# OK1050-C_V1_2_Usb.net
KiCad netlist of a schematic drawn in Altium Designer
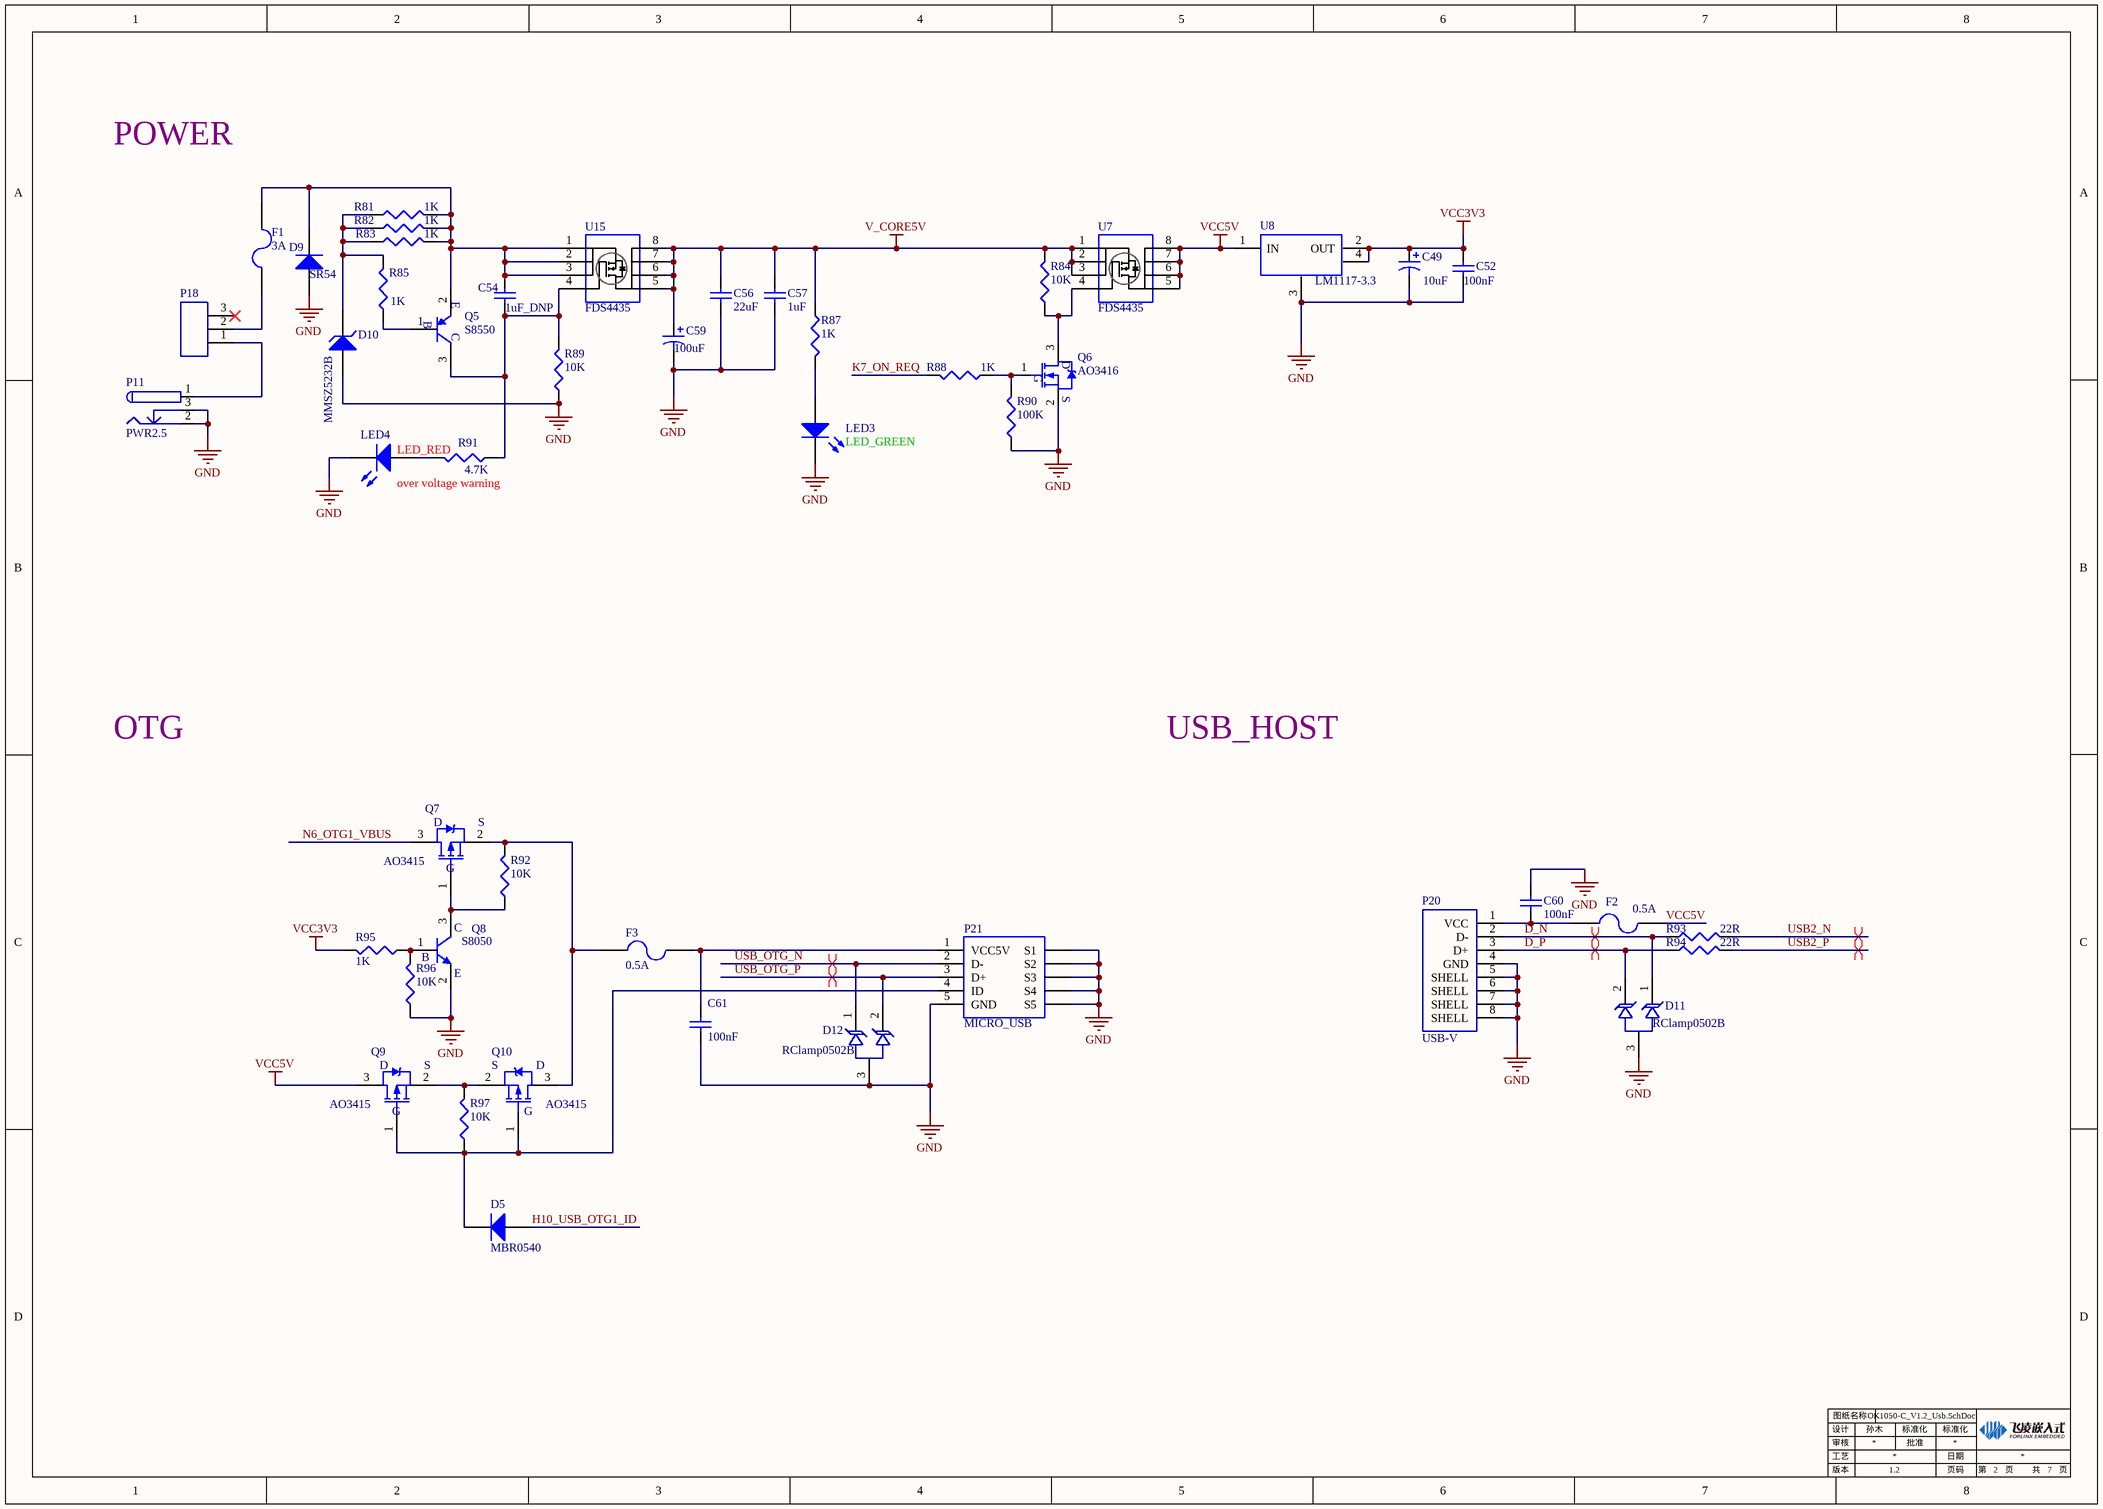
[diagram p0: OK1050-C_V1.2_Usb.SchDoc]

(export (version "E")
  (design (tool "Eeschema 10.0.6"))
  (components
    (comp (ref "C49")
      (value "10uF")
      (footprint "TC3216A")
      (description "Polarized Capacitor (Radial)")
      (fields (field (name "PUBLISHER") "Altium Limited"))
      (libsource (lib "Miscellaneous Devices") (part "Cap Pol1"))
    )
    (comp (ref "C52")
      (value "100nF")
      (footprint "0603C+")
      (description "Capacitor")
      (fields (field (name "PUBLISHER") "Altium Limited"))
      (libsource (lib "Miscellaneous Devices") (part "Cap"))
    )
    (comp (ref "C54")
      (value "1uF_DNP")
      (footprint "0603C+")
      (description "Capacitor")
      (fields (field (name "PUBLISHER") "Altium Limited"))
      (libsource (lib "Miscellaneous Devices") (part "Cap"))
    )
    (comp (ref "C56")
      (value "22uF")
      (footprint "0603C+")
      (description "Capacitor")
      (fields (field (name "PUBLISHER") "Altium Limited"))
      (libsource (lib "Miscellaneous Devices") (part "Cap"))
    )
    (comp (ref "C57")
      (value "1uF")
      (footprint "0603C+")
      (description "Capacitor")
      (fields (field (name "PUBLISHER") "Altium Limited"))
      (libsource (lib "Miscellaneous Devices") (part "Cap"))
    )
    (comp (ref "C59")
      (value "100uF")
      (footprint "TC3528B")
      (description "Polarized Capacitor (Radial)")
      (fields (field (name "PUBLISHER") "Altium Limited"))
      (libsource (lib "Miscellaneous Devices") (part "Cap Pol1"))
    )
    (comp (ref "C60")
      (value "100nF")
      (footprint "0603C+")
      (description "Capacitor")
      (fields (field (name "PUBLISHER") "Altium Limited"))
      (libsource (lib "Miscellaneous Devices") (part "Cap"))
    )
    (comp (ref "C61")
      (value "100nF")
      (footprint "0603C+")
      (description "Capacitor")
      (fields (field (name "PUBLISHER") "Altium Limited"))
      (libsource (lib "Miscellaneous Devices") (part "Cap"))
    )
    (comp (ref "D5")
      (value "MBR0540")
      (footprint "Diode1.6*2.6")
      (description "Default Diode")
      (fields (field (name "PUBLISHER") "Altium Limited"))
      (libsource (lib "Miscellaneous Devices") (part "Diode"))
    )
    (comp (ref "D9")
      (value "SR54")
      (footprint "SMB/DO-214AA")
      (description "Default Diode")
      (fields (field (name "PUBLISHER") "Altium Limited"))
      (libsource (lib "Miscellaneous Devices") (part "Diode"))
    )
    (comp (ref "D10")
      (value "MMSZ5232B")
      (footprint "Diode1.6*2.6")
      (description "Zener Diode")
      (fields (field (name "PUBLISHER") "Altium Limited"))
      (libsource (lib "Miscellaneous Devices") (part "D Zener"))
    )
    (comp (ref "D11") (value "RClamp0502B") (footprint "SOT-523") (libsource (lib "Sch") (part "LCTVS")))
    (comp (ref "D12") (value "RClamp0502B") (footprint "SOT-523") (libsource (lib "Sch") (part "LCTVS")))
    (comp (ref "F1")
      (value "3A")
      (footprint "R_1210")
      (description "Fuse")
      (fields (field (name "PUBLISHER") "Altium Limited"))
      (libsource (lib "Miscellaneous Devices") (part "Fuse 2"))
    )
    (comp (ref "F2")
      (value "0.5A")
      (footprint "R_1210")
      (description "Fuse")
      (fields (field (name "PUBLISHER") "Altium Limited"))
      (libsource (lib "Miscellaneous Devices") (part "Fuse 2"))
    )
    (comp (ref "F3")
      (value "0.5A")
      (footprint "R_1210")
      (description "Fuse")
      (fields (field (name "PUBLISHER") "Altium Limited"))
      (libsource (lib "Miscellaneous Devices") (part "Fuse 2"))
    )
    (comp (ref "LED3")
      (value "LED_GREEN")
      (footprint "LED0603_M1608")
      (description "Typical RED, GREEN, YELLOW, AMBER GaAs LED")
      (fields (field (name "PUBLISHER") "Altium Limited"))
      (libsource (lib "Miscellaneous Devices") (part "LED2"))
    )
    (comp (ref "LED4")
      (value "LED_RED")
      (footprint "LED0603_M1608")
      (description "Typical RED, GREEN, YELLOW, AMBER GaAs LED")
      (fields (field (name "PUBLISHER") "Altium Limited"))
      (libsource (lib "Miscellaneous Devices") (part "LED2"))
    )
    (comp (ref "P11") (value "PWR2.5") (footprint "JACK-2.5MM_B") (libsource (lib "Sch") (part "PWR2.5")))
    (comp (ref "P18") (value "P18") (footprint "SW01") (libsource (lib "Sch") (part "CON3")))
    (comp (ref "P20") (value "USB-V") (footprint "USB-C") (libsource (lib "IMX6QP-C") (part "USB-V")))
    (comp (ref "P21")
      (value "MICRO_USB")
      (footprint "microUSB")
      (description "Header, 5-Pin, Dual row")
      (fields (field (name "PUBLISHER") "Altium Limited"))
      (libsource (lib "PCB_RT1052") (part "MICRO_USB"))
    )
    (comp (ref "Q5")
      (value "S8550")
      (footprint "SOT95P245X110-3N")
      (description "NPN Bipolar Transistor")
      (fields (field (name "PUBLISHER") "Altium Limited"))
      (libsource (lib "KQX6A") (part "PNP"))
    )
    (comp (ref "Q6")
      (value "AO3416")
      (footprint "SOT95P245X110-3N")
      (description "N-Channel Power MOSFET")
      (fields (field (name "PUBLISHER") "Altium Limited"))
      (libsource (lib "IMX6QP-C") (part "NMOS"))
    )
    (comp (ref "Q7")
      (value "AO3415")
      (footprint "SOT95P245X110-3N")
      (description "N-Channel Power MOSFET")
      (fields (field (name "PUBLISHER") "Altium Limited"))
      (libsource (lib "KQX6A") (part "PMOS"))
    )
    (comp (ref "Q8")
      (value "S8050")
      (footprint "SOT95P245X110-3N")
      (description "NPN Bipolar Transistor")
      (fields (field (name "PUBLISHER") "Altium Limited"))
      (libsource (lib "KQX6A") (part "NPN"))
    )
    (comp (ref "Q9")
      (value "AO3415")
      (footprint "SOT95P245X110-3N")
      (description "N-Channel Power MOSFET")
      (fields (field (name "PUBLISHER") "Altium Limited"))
      (libsource (lib "KQX6A") (part "PMOS"))
    )
    (comp (ref "Q10")
      (value "AO3415")
      (footprint "SOT95P245X110-3N")
      (description "N-Channel Power MOSFET")
      (fields (field (name "PUBLISHER") "Altium Limited"))
      (libsource (lib "KQX6A") (part "PMOS"))
    )
    (comp (ref "R81")
      (value "1K")
      (footprint "0603R+")
      (description "Resistor")
      (fields (field (name "PUBLISHER") "Altium Limited"))
      (libsource (lib "Miscellaneous Devices") (part "Res3"))
    )
    (comp (ref "R82")
      (value "1K")
      (footprint "0603R+")
      (description "Resistor")
      (fields (field (name "PUBLISHER") "Altium Limited"))
      (libsource (lib "Miscellaneous Devices") (part "Res3"))
    )
    (comp (ref "R83")
      (value "1K")
      (footprint "0603R+")
      (description "Resistor")
      (fields (field (name "PUBLISHER") "Altium Limited"))
      (libsource (lib "Miscellaneous Devices") (part "Res3"))
    )
    (comp (ref "R84")
      (value "10K")
      (footprint "0603R+")
      (description "Resistor")
      (fields (field (name "PUBLISHER") "Altium Limited"))
      (libsource (lib "Miscellaneous Devices") (part "Res3"))
    )
    (comp (ref "R85")
      (value "1K")
      (footprint "0603R+")
      (description "Resistor")
      (fields (field (name "PUBLISHER") "Altium Limited"))
      (libsource (lib "Miscellaneous Devices") (part "Res3"))
    )
    (comp (ref "R87")
      (value "1K")
      (footprint "0603R+")
      (description "Resistor")
      (fields (field (name "PUBLISHER") "Altium Limited"))
      (libsource (lib "Miscellaneous Devices") (part "Res3"))
    )
    (comp (ref "R88")
      (value "1K")
      (footprint "0603R+")
      (description "Resistor")
      (fields (field (name "PUBLISHER") "Altium Limited"))
      (libsource (lib "Miscellaneous Devices") (part "Res3"))
    )
    (comp (ref "R89")
      (value "10K")
      (footprint "0603R+")
      (description "Resistor")
      (fields (field (name "PUBLISHER") "Altium Limited"))
      (libsource (lib "Miscellaneous Devices") (part "Res3"))
    )
    (comp (ref "R90")
      (value "100K")
      (footprint "0603R+")
      (description "Resistor")
      (fields (field (name "PUBLISHER") "Altium Limited"))
      (libsource (lib "Miscellaneous Devices") (part "Res3"))
    )
    (comp (ref "R91")
      (value "4.7K")
      (footprint "0603R+")
      (description "Resistor")
      (fields (field (name "PUBLISHER") "Altium Limited"))
      (libsource (lib "Miscellaneous Devices") (part "Res3"))
    )
    (comp (ref "R92")
      (value "10K")
      (footprint "0603R+")
      (description "Resistor")
      (fields (field (name "PUBLISHER") "Altium Limited"))
      (libsource (lib "Miscellaneous Devices") (part "Res3"))
    )
    (comp (ref "R93")
      (value "22R")
      (footprint "0603R+")
      (description "Resistor")
      (fields (field (name "PUBLISHER") "Altium Limited"))
      (libsource (lib "Miscellaneous Devices") (part "Res3"))
    )
    (comp (ref "R94")
      (value "22R")
      (footprint "0603R+")
      (description "Resistor")
      (fields (field (name "PUBLISHER") "Altium Limited"))
      (libsource (lib "Miscellaneous Devices") (part "Res3"))
    )
    (comp (ref "R95")
      (value "1K")
      (footprint "0603R+")
      (description "Resistor")
      (fields (field (name "PUBLISHER") "Altium Limited"))
      (libsource (lib "Miscellaneous Devices") (part "Res3"))
    )
    (comp (ref "R96")
      (value "10K")
      (footprint "0603R+")
      (description "Resistor")
      (fields (field (name "PUBLISHER") "Altium Limited"))
      (libsource (lib "Miscellaneous Devices") (part "Res3"))
    )
    (comp (ref "R97")
      (value "10K")
      (footprint "0603R+")
      (description "Resistor")
      (fields (field (name "PUBLISHER") "Altium Limited"))
      (libsource (lib "Miscellaneous Devices") (part "Res3"))
    )
    (comp (ref "U7") (value "FDS4435") (footprint "FDS4435") (libsource (lib "OK5718") (part "FDS4435")))
    (comp (ref "U8") (value "LM1117-3.3") (footprint "LM1117") (libsource (lib "Sch") (part "LM1117")))
    (comp (ref "U15") (value "FDS4435") (footprint "FDS4435") (libsource (lib "OK5718") (part "FDS4435")))
  )
  (nets
    (net (code "1") (name "/D_N") (class "Default")
      (node (ref "D11") (pin "1") (pinfunction "1_1") (pintype "passive"))
      (node (ref "P20") (pin "2") (pinfunction "D-_2") (pintype "passive"))
      (node (ref "R93") (pin "1") (pinfunction "1_1") (pintype "passive"))
    )
    (net (code "2") (name "/D_P") (class "Default")
      (node (ref "D11") (pin "2") (pinfunction "2_2") (pintype "passive"))
      (node (ref "P20") (pin "3") (pinfunction "D+_3") (pintype "passive"))
      (node (ref "R94") (pin "1") (pinfunction "1_1") (pintype "passive"))
    )
    (net (code "3") (name "/H10_USB_OTG1_ID") (class "Default")
      (node (ref "D5") (pin "1") (pinfunction "A_1") (pintype "passive"))
    )
    (net (code "4") (name "/K7_ON_REQ") (class "Default")
      (node (ref "R88") (pin "2") (pinfunction "2_2") (pintype "passive"))
    )
    (net (code "5") (name "/N6_OTG1_VBUS") (class "Default")
      (node (ref "Q7") (pin "3") (pinfunction "D_3") (pintype "passive"))
    )
    (net (code "6") (name "/USB2_N") (class "Default")
      (node (ref "R93") (pin "2") (pinfunction "2_2") (pintype "passive"))
    )
    (net (code "7") (name "/USB2_P") (class "Default")
      (node (ref "R94") (pin "2") (pinfunction "2_2") (pintype "passive"))
    )
    (net (code "8") (name "/USB_OTG_N") (class "Default")
      (node (ref "D12") (pin "1") (pinfunction "1_1") (pintype "passive"))
      (node (ref "P21") (pin "2") (pinfunction "D-_2") (pintype "passive"))
    )
    (net (code "9") (name "/USB_OTG_P") (class "Default")
      (node (ref "D12") (pin "2") (pinfunction "2_2") (pintype "passive"))
      (node (ref "P21") (pin "3") (pinfunction "D+_3") (pintype "passive"))
    )
    (net (code "10") (name "GND") (class "Default")
      (node (ref "C49") (pin "2") (pinfunction "2_2") (pintype "passive"))
      (node (ref "C52") (pin "1") (pinfunction "1_1") (pintype "passive"))
      (node (ref "C56") (pin "2") (pinfunction "2_2") (pintype "passive"))
      (node (ref "C57") (pin "2") (pinfunction "2_2") (pintype "passive"))
      (node (ref "C59") (pin "2") (pinfunction "2_2") (pintype "passive"))
      (node (ref "C60") (pin "1") (pinfunction "1_1") (pintype "passive"))
      (node (ref "C61") (pin "1") (pinfunction "1_1") (pintype "passive"))
      (node (ref "D10") (pin "1") (pinfunction "A_1") (pintype "passive"))
      (node (ref "D11") (pin "3") (pintype "passive"))
      (node (ref "D12") (pin "3") (pintype "passive"))
      (node (ref "D9") (pin "1") (pinfunction "A_1") (pintype "passive"))
      (node (ref "LED3") (pin "2") (pinfunction "K_2") (pintype "passive"))
      (node (ref "LED4") (pin "2") (pinfunction "K_2") (pintype "passive"))
      (node (ref "P11") (pin "2") (pinfunction "ADJ_2") (pintype "passive"))
      (node (ref "P11") (pin "3") (pinfunction "ADJ_3") (pintype "passive"))
      (node (ref "P20") (pin "4") (pinfunction "GND_4") (pintype "passive"))
      (node (ref "P20") (pin "5") (pinfunction "SHELL_5") (pintype "passive"))
      (node (ref "P20") (pin "6") (pinfunction "SHELL_6") (pintype "passive"))
      (node (ref "P20") (pin "7") (pinfunction "SHELL_7") (pintype "passive"))
      (node (ref "P20") (pin "8") (pinfunction "SHELL_8") (pintype "passive"))
      (node (ref "P21") (pin "10") (pinfunction "S5_10") (pintype "passive"))
      (node (ref "P21") (pin "5") (pinfunction "GND_5") (pintype "passive"))
      (node (ref "P21") (pin "6") (pinfunction "S1_6") (pintype "passive"))
      (node (ref "P21") (pin "7") (pinfunction "S2_7") (pintype "passive"))
      (node (ref "P21") (pin "8") (pinfunction "S3_8") (pintype "passive"))
      (node (ref "P21") (pin "9") (pinfunction "S4_9") (pintype "passive"))
      (node (ref "Q6") (pin "2") (pinfunction "S_2") (pintype "passive"))
      (node (ref "Q8") (pin "2") (pinfunction "E_2") (pintype "passive"))
      (node (ref "R89") (pin "1") (pinfunction "1_1") (pintype "passive"))
      (node (ref "R90") (pin "1") (pinfunction "1_1") (pintype "passive"))
      (node (ref "R96") (pin "1") (pinfunction "1_1") (pintype "passive"))
      (node (ref "U8") (pin "3") (pinfunction "GND_3") (pintype "passive"))
    )
    (net (code "11") (name "Net-(D5-K)") (class "Default")
      (node (ref "D5") (pin "2") (pinfunction "K_2") (pintype "passive"))
      (node (ref "P21") (pin "4") (pinfunction "ID_4") (pintype "passive"))
      (node (ref "Q10") (pin "1") (pinfunction "G_1") (pintype "passive"))
      (node (ref "Q9") (pin "1") (pinfunction "G_1") (pintype "passive"))
      (node (ref "R97") (pin "1") (pinfunction "1_1") (pintype "passive"))
    )
    (net (code "12") (name "Net-(D9-K)") (class "Default")
      (node (ref "C54") (pin "1") (pinfunction "1_1") (pintype "passive"))
      (node (ref "D9") (pin "2") (pinfunction "K_2") (pintype "passive"))
      (node (ref "F1") (pin "2") (pinfunction "2_2") (pintype "passive"))
      (node (ref "Q5") (pin "2") (pinfunction "E_2") (pintype "passive"))
      (node (ref "R81") (pin "2") (pinfunction "2_2") (pintype "passive"))
      (node (ref "R82") (pin "2") (pinfunction "2_2") (pintype "passive"))
      (node (ref "R83") (pin "2") (pinfunction "2_2") (pintype "passive"))
      (node (ref "U15") (pin "1") (pinfunction "S_1") (pintype "passive"))
      (node (ref "U15") (pin "2") (pinfunction "S_2") (pintype "passive"))
      (node (ref "U15") (pin "3") (pinfunction "S_3") (pintype "passive"))
    )
    (net (code "13") (name "Net-(D10-K)") (class "Default")
      (node (ref "D10") (pin "2") (pinfunction "K_2") (pintype "passive"))
      (node (ref "R81") (pin "1") (pinfunction "1_1") (pintype "passive"))
      (node (ref "R82") (pin "1") (pinfunction "1_1") (pintype "passive"))
      (node (ref "R83") (pin "1") (pinfunction "1_1") (pintype "passive"))
      (node (ref "R85") (pin "2") (pinfunction "2_2") (pintype "passive"))
    )
    (net (code "14") (name "Net-(LED3-A)") (class "Default")
      (node (ref "LED3") (pin "1") (pinfunction "A_1") (pintype "passive"))
      (node (ref "R87") (pin "2") (pinfunction "2_2") (pintype "passive"))
    )
    (net (code "15") (name "Net-(LED4-A)") (class "Default")
      (node (ref "LED4") (pin "1") (pinfunction "A_1") (pintype "passive"))
      (node (ref "R91") (pin "2") (pinfunction "2_2") (pintype "passive"))
    )
    (net (code "16") (name "Net-(P18-DQ16)") (class "Default")
      (node (ref "P11") (pin "1") (pinfunction "ADJ_1") (pintype "passive"))
      (node (ref "P18") (pin "1") (pinfunction "DQ16_1") (pintype "passive"))
    )
    (net (code "17") (name "Net-(P18-DQ17)") (class "Default")
      (node (ref "F1") (pin "1") (pinfunction "1_1") (pintype "passive"))
      (node (ref "P18") (pin "2") (pinfunction "DQ17_2") (pintype "passive"))
    )
    (net (code "18") (name "Net-(P20-VCC)") (class "Default")
      (node (ref "C60") (pin "2") (pinfunction "2_2") (pintype "passive"))
      (node (ref "F2") (pin "2") (pinfunction "2_2") (pintype "passive"))
      (node (ref "P20") (pin "1") (pinfunction "VCC_1") (pintype "passive"))
    )
    (net (code "19") (name "Net-(P21-VCC5V)") (class "Default")
      (node (ref "C61") (pin "2") (pinfunction "2_2") (pintype "passive"))
      (node (ref "F3") (pin "1") (pinfunction "1_1") (pintype "passive"))
      (node (ref "P21") (pin "1") (pinfunction "VCC5V_1") (pintype "passive"))
    )
    (net (code "20") (name "Net-(Q5-B)") (class "Default")
      (node (ref "Q5") (pin "1") (pinfunction "B_1") (pintype "passive"))
      (node (ref "R85") (pin "1") (pinfunction "1_1") (pintype "passive"))
    )
    (net (code "21") (name "Net-(Q5-C)") (class "Default")
      (node (ref "C54") (pin "2") (pinfunction "2_2") (pintype "passive"))
      (node (ref "Q5") (pin "3") (pinfunction "C_3") (pintype "passive"))
      (node (ref "R89") (pin "2") (pinfunction "2_2") (pintype "passive"))
      (node (ref "R91") (pin "1") (pinfunction "1_1") (pintype "passive"))
      (node (ref "U15") (pin "4") (pinfunction "G_4") (pintype "passive"))
    )
    (net (code "22") (name "Net-(Q6-D)") (class "Default")
      (node (ref "Q6") (pin "3") (pinfunction "D_3") (pintype "passive"))
      (node (ref "R84") (pin "1") (pinfunction "1_1") (pintype "passive"))
      (node (ref "U7") (pin "4") (pinfunction "G_4") (pintype "passive"))
    )
    (net (code "23") (name "Net-(Q6-G)") (class "Default")
      (node (ref "Q6") (pin "1") (pinfunction "G_1") (pintype "passive"))
      (node (ref "R88") (pin "1") (pinfunction "1_1") (pintype "passive"))
      (node (ref "R90") (pin "2") (pinfunction "2_2") (pintype "passive"))
    )
    (net (code "24") (name "Net-(Q7-G)") (class "Default")
      (node (ref "Q7") (pin "1") (pinfunction "G_1") (pintype "passive"))
      (node (ref "Q8") (pin "3") (pinfunction "C_3") (pintype "passive"))
      (node (ref "R92") (pin "1") (pinfunction "1_1") (pintype "passive"))
    )
    (net (code "25") (name "Net-(Q8-B)") (class "Default")
      (node (ref "Q8") (pin "1") (pinfunction "B_1") (pintype "passive"))
      (node (ref "R95") (pin "1") (pinfunction "1_1") (pintype "passive"))
      (node (ref "R96") (pin "2") (pinfunction "2_2") (pintype "passive"))
    )
    (net (code "26") (name "Net-(Q10-D)") (class "Default")
      (node (ref "F3") (pin "2") (pinfunction "2_2") (pintype "passive"))
      (node (ref "Q10") (pin "3") (pinfunction "D_3") (pintype "passive"))
      (node (ref "Q7") (pin "2") (pinfunction "S_2") (pintype "passive"))
      (node (ref "R92") (pin "2") (pinfunction "2_2") (pintype "passive"))
    )
    (net (code "27") (name "Net-(Q10-S)") (class "Default")
      (node (ref "Q10") (pin "2") (pinfunction "S_2") (pintype "passive"))
      (node (ref "Q9") (pin "2") (pinfunction "S_2") (pintype "passive"))
      (node (ref "R97") (pin "2") (pinfunction "2_2") (pintype "passive"))
    )
    (net (code "28") (name "VCC3V3") (class "Default")
      (node (ref "C49") (pin "1") (pinfunction "1_1") (pintype "passive"))
      (node (ref "C52") (pin "2") (pinfunction "2_2") (pintype "passive"))
      (node (ref "R95") (pin "2") (pinfunction "2_2") (pintype "passive"))
      (node (ref "U8") (pin "2") (pinfunction "OUT_2") (pintype "passive"))
      (node (ref "U8") (pin "4") (pintype "passive"))
    )
    (net (code "29") (name "VCC5V") (class "Default")
      (node (ref "F2") (pin "1") (pinfunction "1_1") (pintype "passive"))
      (node (ref "Q9") (pin "3") (pinfunction "D_3") (pintype "passive"))
      (node (ref "U7") (pin "5") (pinfunction "D_5") (pintype "passive"))
      (node (ref "U7") (pin "6") (pinfunction "D_6") (pintype "passive"))
      (node (ref "U7") (pin "7") (pinfunction "D_7") (pintype "passive"))
      (node (ref "U7") (pin "8") (pinfunction "D_8") (pintype "passive"))
      (node (ref "U8") (pin "1") (pinfunction "IN_1") (pintype "passive"))
    )
    (net (code "30") (name "V_CORE5V") (class "Default")
      (node (ref "C56") (pin "1") (pinfunction "1_1") (pintype "passive"))
      (node (ref "C57") (pin "1") (pinfunction "1_1") (pintype "passive"))
      (node (ref "C59") (pin "1") (pinfunction "1_1") (pintype "passive"))
      (node (ref "R84") (pin "2") (pinfunction "2_2") (pintype "passive"))
      (node (ref "R87") (pin "1") (pinfunction "1_1") (pintype "passive"))
      (node (ref "U15") (pin "5") (pinfunction "D_5") (pintype "passive"))
      (node (ref "U15") (pin "6") (pinfunction "D_6") (pintype "passive"))
      (node (ref "U15") (pin "7") (pinfunction "D_7") (pintype "passive"))
      (node (ref "U15") (pin "8") (pinfunction "D_8") (pintype "passive"))
      (node (ref "U7") (pin "1") (pinfunction "S_1") (pintype "passive"))
      (node (ref "U7") (pin "2") (pinfunction "S_2") (pintype "passive"))
      (node (ref "U7") (pin "3") (pinfunction "S_3") (pintype "passive"))
    )
    (net (code "31") (name "unconnected-(P18-DQ18-Pad3)") (class "Default")
      (node (ref "P18") (pin "3") (pinfunction "DQ18_3") (pintype "passive+no_connect"))
    )
  )
)
